# Antenna_Board_v4_4.net
KiCad netlist of a schematic drawn in EAGLE
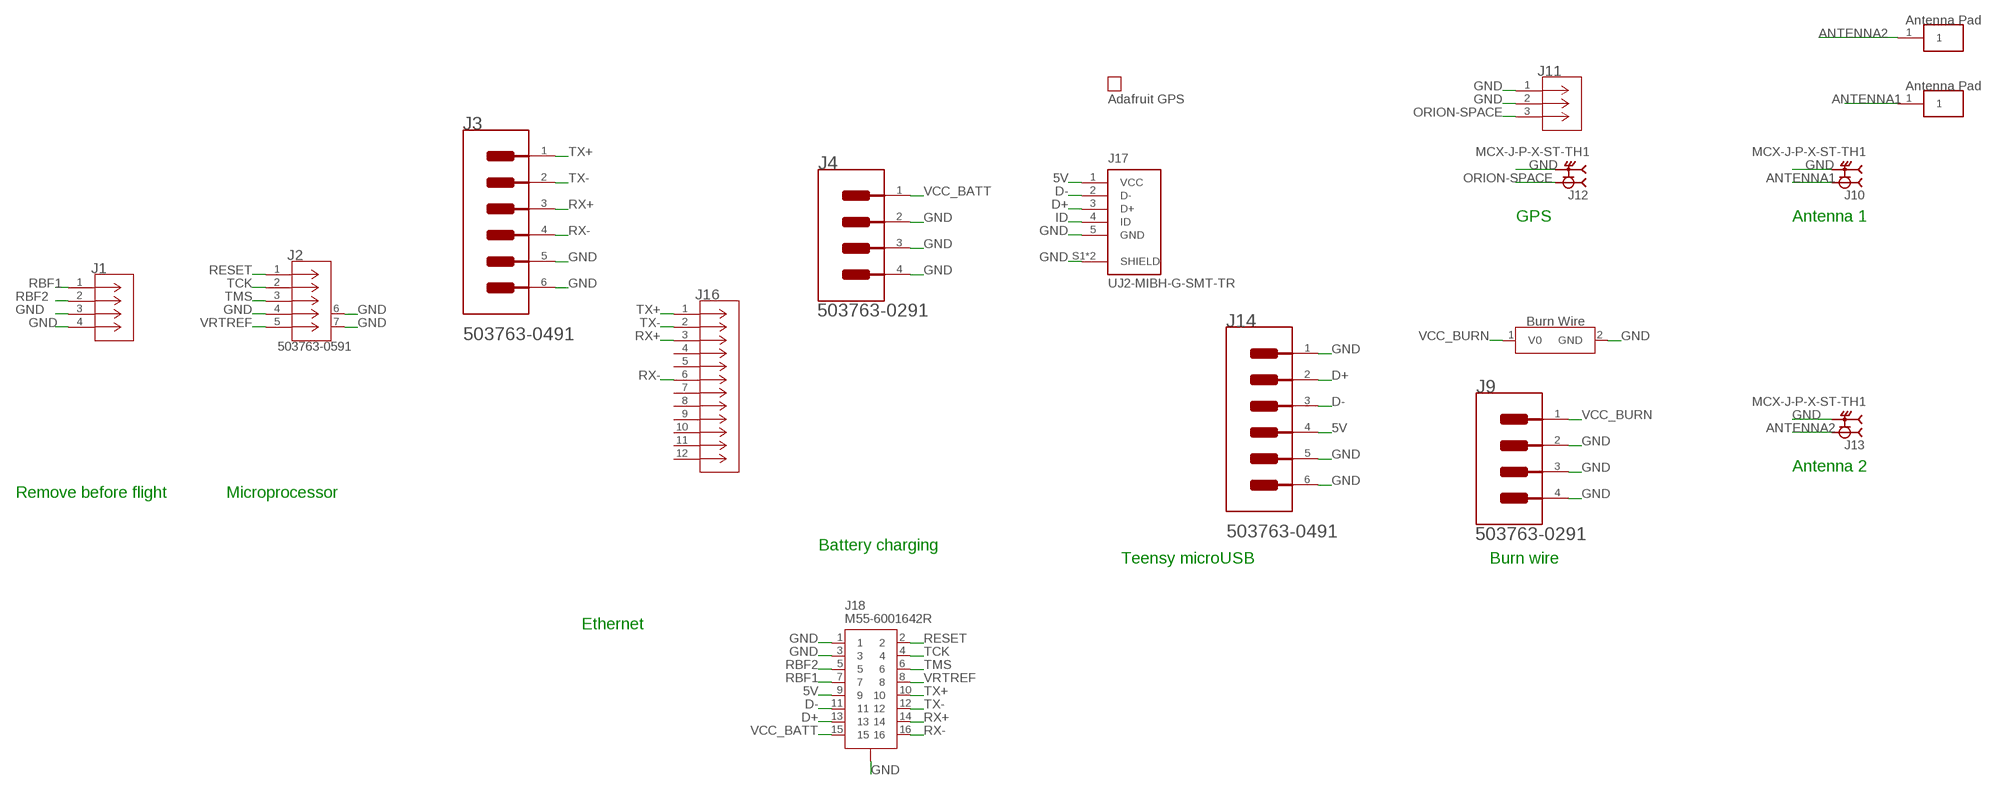
[diagram p0: schematic, sheet 1]

(export (version "E")
  (design (tool "Eeschema 10.0.6"))
  (components
    (comp (ref "GPS")
      (value "PA1010D")
      (footprint "eagle-import:PA1010D")
      (libsource (lib "eagle-import") (part "PA1010D"))
    )
    (comp (ref "J1")
      (value "5037630291")
      (footprint "eagle-import:CON_5037630291")
      (fields (field (name "COPYRIGHT") "Copyright (C) 2018 Accelerated Designs. All rights reserved"))
      (libsource (lib "eagle-import") (part "5037630291"))
    )
    (comp (ref "J2")
      (value "503763-0591")
      (footprint "eagle-import:CONN_5037630591_MOL")
      (fields (field (name "COPYRIGHT") "Copyright (C) 2018 Accelerated Designs. All rights reserved"))
      (libsource (lib "eagle-import") (part "503763-0591"))
    )
    (comp (ref "J3")
      (value "MOLEX_503763-0491MOLEX_503763-0491_0_0")
      (footprint "eagle-import:MOLEX_503763-0491_0")
      (fields
        (field (name "DIGIKEY_PART_NUMBER") "WM10655CT-ND")
        (field (name "MF") "Molex")
        (field (name "MOUSER_PART_NUMBER") "538-503763-0491")
      )
      (libsource (lib "eagle-import") (part "MOLEX_503763-0491MOLEX_503763-0491_0_0"))
    )
    (comp (ref "J4")
      (value "MOLEX_503763-0291MOLEX_503763-0291_0_0")
      (footprint "eagle-import:MOLEX_503763-0291_0")
      (fields
        (field (name "DIGIKEY_PART_NUMBER") "WM10654CT-ND")
        (field (name "MF") "Molex")
        (field (name "MOUSER_PART_NUMBER") "538-503763-0291")
      )
      (libsource (lib "eagle-import") (part "MOLEX_503763-0291MOLEX_503763-0291_0_0"))
    )
    (comp (ref "J9")
      (value "MOLEX_503763-0291MOLEX_503763-0291_0_0")
      (footprint "eagle-import:MOLEX_503763-0291_0")
      (fields
        (field (name "DIGIKEY_PART_NUMBER") "WM10654CT-ND")
        (field (name "MF") "Molex")
        (field (name "MOUSER_PART_NUMBER") "538-503763-0291")
      )
      (libsource (lib "eagle-import") (part "MOLEX_503763-0291MOLEX_503763-0291_0_0"))
    )
    (comp (ref "J10")
      (value "MCX-J-P-X-ST-TH1")
      (footprint "eagle-import:SAMTEC_MCX-J-P-X-ST-TH1")
      (fields
        (field (name "DIGI-KEY_PART_NUMBER") "SAM8944-ND")
        (field (name "MF") "Samtec")
        (field (name "MP") "MCX-J-P-H-ST-TH1")
      )
      (libsource (lib "eagle-import") (part "MCX-J-P-X-ST-TH1"))
    )
    (comp (ref "J11")
      (value "U.FL-R-SMT-1(01)")
      (footprint "eagle-import:CONN_-SMT-1(01)")
      (fields (field (name "COPYRIGHT") "Copyright (C) 2018 Accelerated Designs. All rights reserved"))
      (libsource (lib "eagle-import") (part "U.FL-R-SMT-1(01)"))
    )
    (comp (ref "J12")
      (value "MCX-J-P-X-ST-TH1")
      (footprint "eagle-import:SAMTEC_MCX-J-P-X-ST-TH1")
      (fields
        (field (name "DIGI-KEY_PART_NUMBER") "SAM8944-ND")
        (field (name "MF") "Samtec")
        (field (name "MP") "MCX-J-P-H-ST-TH1")
      )
      (libsource (lib "eagle-import") (part "MCX-J-P-X-ST-TH1"))
    )
    (comp (ref "J13")
      (value "MCX-J-P-X-ST-TH1")
      (footprint "eagle-import:SAMTEC_MCX-J-P-X-ST-TH1")
      (fields
        (field (name "DIGI-KEY_PART_NUMBER") "SAM8944-ND")
        (field (name "MF") "Samtec")
        (field (name "MP") "MCX-J-P-H-ST-TH1")
      )
      (libsource (lib "eagle-import") (part "MCX-J-P-X-ST-TH1"))
    )
    (comp (ref "J14")
      (value "MOLEX_503763-0491MOLEX_503763-0491_0_0")
      (footprint "eagle-import:MOLEX_503763-0491_0")
      (fields
        (field (name "DIGIKEY_PART_NUMBER") "WM10655CT-ND")
        (field (name "MF") "Molex")
        (field (name "MOUSER_PART_NUMBER") "538-503763-0491")
      )
      (libsource (lib "eagle-import") (part "MOLEX_503763-0491MOLEX_503763-0491_0_0"))
    )
    (comp (ref "J16")
      (value "ARJM11C7-104-AB-EW2")
      (footprint "eagle-import:CONN_EW_ABR")
      (libsource (lib "eagle-import") (part "ARJM11C7-104-AB-EW2"))
    )
    (comp (ref "J17")
      (value "UJ2-MIBH-G-SMT-TR")
      (footprint "eagle-import:CUI_UJ2-MIBH-G-SMT-TR")
      (fields
        (field (name "DIGI-KEY_PART_NUMBER") "2223-UJ2-MIBH-G-SMT-TRCT-ND")
        (field (name "MF") "CUI Devices")
      )
      (libsource (lib "eagle-import") (part "UJ2-MIBH-G-SMT-TR"))
    )
    (comp (ref "J18")
      (value "M55-6001642R")
      (footprint "eagle-import:CONN_M55-6001642R_HRW")
      (fields (field (name "COPYRIGHT") "Copyright (C) 2021 Ultra Librarian. All rights reserved."))
      (libsource (lib "eagle-import") (part "M55-6001642R"))
    )
    (comp (ref "U$1")
      (value "ANTENNA_PAD")
      (footprint "eagle-import:ANTENNA_PAD")
      (libsource (lib "eagle-import") (part "ANTENNA_PAD"))
    )
    (comp (ref "U$2")
      (value "ANTENNA_PAD")
      (footprint "eagle-import:ANTENNA_PAD")
      (libsource (lib "eagle-import") (part "ANTENNA_PAD"))
    )
    (comp (ref "U$3")
      (value "BURNWIRE")
      (footprint "eagle-import:BURNWIRE")
      (libsource (lib "eagle-import") (part "BURNWIRE"))
    )
  )
  (nets
    (net (code "1") (name "/5V") (class "Default")
      (node (ref "J14") (pin "4") (pinfunction "4_4") (pintype "passive"))
      (node (ref "J17") (pin "1") (pinfunction "VCC_1") (pintype "power_in"))
      (node (ref "J18") (pin "9") (pinfunction "9_9") (pintype "passive"))
    )
    (net (code "2") (name "/ANTENNA1") (class "Default")
      (node (ref "J10") (pin "1") (pinfunction "1_1") (pintype "passive"))
      (node (ref "U$2") (pin "1") (pinfunction "1_1") (pintype "bidirectional"))
    )
    (net (code "3") (name "/ANTENNA2") (class "Default")
      (node (ref "J13") (pin "1") (pinfunction "1_1") (pintype "passive"))
      (node (ref "U$1") (pin "1") (pinfunction "1_1") (pintype "bidirectional"))
    )
    (net (code "4") (name "/D+") (class "Default")
      (node (ref "J14") (pin "2") (pinfunction "2_2") (pintype "passive"))
      (node (ref "J17") (pin "3") (pinfunction "D+_3") (pintype "bidirectional"))
      (node (ref "J18") (pin "13") (pinfunction "13_13") (pintype "passive"))
    )
    (net (code "5") (name "/D-") (class "Default")
      (node (ref "J14") (pin "3") (pinfunction "3_3") (pintype "passive"))
      (node (ref "J17") (pin "2") (pinfunction "D-_2") (pintype "bidirectional"))
      (node (ref "J18") (pin "11") (pinfunction "11_11") (pintype "passive"))
    )
    (net (code "6") (name "/GND") (class "Default")
      (node (ref "J1") (pin "3") (pinfunction "3_3") (pintype "passive"))
      (node (ref "J1") (pin "4") (pinfunction "4_4") (pintype "passive"))
      (node (ref "J10") (pin "S1") (pinfunction "2_S1") (pintype "passive"))
      (node (ref "J10") (pin "S2") (pinfunction "2_S2") (pintype "passive"))
      (node (ref "J10") (pin "S3") (pinfunction "2_S3") (pintype "passive"))
      (node (ref "J10") (pin "S4") (pinfunction "2_S4") (pintype "passive"))
      (node (ref "J11") (pin "1") (pinfunction "1_1") (pintype "passive"))
      (node (ref "J11") (pin "2") (pinfunction "2_2") (pintype "passive"))
      (node (ref "J12") (pin "S1") (pinfunction "2_S1") (pintype "passive"))
      (node (ref "J12") (pin "S2") (pinfunction "2_S2") (pintype "passive"))
      (node (ref "J12") (pin "S3") (pinfunction "2_S3") (pintype "passive"))
      (node (ref "J12") (pin "S4") (pinfunction "2_S4") (pintype "passive"))
      (node (ref "J13") (pin "S1") (pinfunction "2_S1") (pintype "passive"))
      (node (ref "J13") (pin "S2") (pinfunction "2_S2") (pintype "passive"))
      (node (ref "J13") (pin "S3") (pinfunction "2_S3") (pintype "passive"))
      (node (ref "J13") (pin "S4") (pinfunction "2_S4") (pintype "passive"))
      (node (ref "J14") (pin "1") (pinfunction "1_1") (pintype "passive"))
      (node (ref "J14") (pin "5") (pinfunction "MNT_1_5") (pintype "passive"))
      (node (ref "J14") (pin "6") (pinfunction "MNT_2_6") (pintype "passive"))
      (node (ref "J17") (pin "5") (pinfunction "GND_5") (pintype "power_in"))
      (node (ref "J17") (pin "S1") (pinfunction "SHIELD_S1") (pintype "passive"))
      (node (ref "J17") (pin "S2") (pinfunction "SHIELD_S2") (pintype "passive"))
      (node (ref "J18") (pin "1") (pinfunction "1_1") (pintype "passive"))
      (node (ref "J18") (pin "19") (pinfunction "17_19") (pintype "passive"))
      (node (ref "J18") (pin "20") (pinfunction "17_20") (pintype "passive"))
      (node (ref "J18") (pin "21") (pinfunction "17_21") (pintype "passive"))
      (node (ref "J18") (pin "22") (pinfunction "17_22") (pintype "passive"))
      (node (ref "J18") (pin "3") (pinfunction "3_3") (pintype "passive"))
      (node (ref "J2") (pin "4") (pinfunction "4_4") (pintype "passive"))
      (node (ref "J2") (pin "6") (pinfunction "6_6") (pintype "bidirectional"))
      (node (ref "J2") (pin "7") (pinfunction "7_7") (pintype "bidirectional"))
      (node (ref "J3") (pin "5") (pinfunction "MNT_1_5") (pintype "passive"))
      (node (ref "J3") (pin "6") (pinfunction "MNT_2_6") (pintype "passive"))
      (node (ref "J4") (pin "2") (pinfunction "2_2") (pintype "bidirectional"))
      (node (ref "J4") (pin "3") (pinfunction "MNT_1_3") (pintype "bidirectional"))
      (node (ref "J4") (pin "4") (pinfunction "MNT_2_4") (pintype "bidirectional"))
      (node (ref "J9") (pin "2") (pinfunction "2_2") (pintype "bidirectional"))
      (node (ref "J9") (pin "3") (pinfunction "MNT_1_3") (pintype "bidirectional"))
      (node (ref "J9") (pin "4") (pinfunction "MNT_2_4") (pintype "bidirectional"))
      (node (ref "U$3") (pin "2") (pinfunction "GND_2") (pintype "bidirectional"))
    )
    (net (code "7") (name "/ID") (class "Default")
      (node (ref "J17") (pin "4") (pinfunction "ID_4") (pintype "bidirectional"))
    )
    (net (code "8") (name "/ORION-SPACE") (class "Default")
      (node (ref "J11") (pin "3") (pinfunction "3_3") (pintype "passive"))
      (node (ref "J12") (pin "1") (pinfunction "1_1") (pintype "passive"))
    )
    (net (code "9") (name "/RBF1") (class "Default")
      (node (ref "J1") (pin "1") (pinfunction "1_1") (pintype "passive"))
      (node (ref "J18") (pin "7") (pinfunction "7_7") (pintype "passive"))
    )
    (net (code "10") (name "/RBF2") (class "Default")
      (node (ref "J1") (pin "2") (pinfunction "2_2") (pintype "passive"))
      (node (ref "J18") (pin "5") (pinfunction "5_5") (pintype "passive"))
    )
    (net (code "11") (name "/RESET") (class "Default")
      (node (ref "J18") (pin "2") (pinfunction "2_2") (pintype "passive"))
      (node (ref "J2") (pin "1") (pinfunction "1_1") (pintype "passive"))
    )
    (net (code "12") (name "/RX+") (class "Default")
      (node (ref "J16") (pin "3") (pinfunction "3_3") (pintype "passive"))
      (node (ref "J18") (pin "14") (pinfunction "14_14") (pintype "passive"))
      (node (ref "J3") (pin "3") (pinfunction "3_3") (pintype "passive"))
    )
    (net (code "13") (name "/RX-") (class "Default")
      (node (ref "J16") (pin "6") (pinfunction "6_6") (pintype "passive"))
      (node (ref "J18") (pin "16") (pinfunction "16_16") (pintype "passive"))
      (node (ref "J3") (pin "4") (pinfunction "4_4") (pintype "passive"))
    )
    (net (code "14") (name "/TCK") (class "Default")
      (node (ref "J18") (pin "4") (pinfunction "4_4") (pintype "passive"))
      (node (ref "J2") (pin "2") (pinfunction "2_2") (pintype "passive"))
    )
    (net (code "15") (name "/TMS") (class "Default")
      (node (ref "J18") (pin "6") (pinfunction "6_6") (pintype "passive"))
      (node (ref "J2") (pin "3") (pinfunction "3_3") (pintype "passive"))
    )
    (net (code "16") (name "/TX+") (class "Default")
      (node (ref "J16") (pin "1") (pinfunction "1_1") (pintype "passive"))
      (node (ref "J18") (pin "10") (pinfunction "10_10") (pintype "passive"))
      (node (ref "J3") (pin "1") (pinfunction "1_1") (pintype "passive"))
    )
    (net (code "17") (name "/TX-") (class "Default")
      (node (ref "J16") (pin "2") (pinfunction "2_2") (pintype "passive"))
      (node (ref "J18") (pin "12") (pinfunction "12_12") (pintype "passive"))
      (node (ref "J3") (pin "2") (pinfunction "2_2") (pintype "passive"))
    )
    (net (code "18") (name "/VCC_BATT") (class "Default")
      (node (ref "J18") (pin "15") (pinfunction "15_15") (pintype "passive"))
      (node (ref "J4") (pin "1") (pinfunction "1_1") (pintype "bidirectional"))
    )
    (net (code "19") (name "/VCC_BURN") (class "Default")
      (node (ref "J9") (pin "1") (pinfunction "1_1") (pintype "bidirectional"))
      (node (ref "U$3") (pin "1") (pinfunction "V0_1") (pintype "bidirectional"))
    )
    (net (code "20") (name "/VRTREF") (class "Default")
      (node (ref "J18") (pin "8") (pinfunction "8_8") (pintype "passive"))
      (node (ref "J2") (pin "5") (pinfunction "5_5") (pintype "passive"))
    )
    (net (code "21") (name "unconnected-(J16-Pad4)") (class "Default")
      (node (ref "J16") (pin "4") (pinfunction "4_4") (pintype "passive"))
    )
    (net (code "22") (name "unconnected-(J16-Pad5)") (class "Default")
      (node (ref "J16") (pin "5") (pinfunction "5_5") (pintype "passive"))
    )
    (net (code "23") (name "unconnected-(J16-Pad7)") (class "Default")
      (node (ref "J16") (pin "7") (pinfunction "7_7") (pintype "passive"))
    )
    (net (code "24") (name "unconnected-(J16-Pad8)") (class "Default")
      (node (ref "J16") (pin "8") (pinfunction "8_8") (pintype "passive"))
    )
    (net (code "25") (name "unconnected-(J16-Pad9)") (class "Default")
      (node (ref "J16") (pin "9") (pinfunction "9_9") (pintype "passive"))
    )
    (net (code "26") (name "unconnected-(J16-Pad10)") (class "Default")
      (node (ref "J16") (pin "10") (pinfunction "10_10") (pintype "passive"))
    )
    (net (code "27") (name "unconnected-(J16-Pad11)") (class "Default")
      (node (ref "J16") (pin "11") (pinfunction "11_11") (pintype "passive"))
    )
    (net (code "28") (name "unconnected-(J16-Pad12)") (class "Default")
      (node (ref "J16") (pin "12") (pinfunction "12_12") (pintype "passive"))
    )
  )
)
